# FFD.net
KiCad netlist of a schematic drawn in Altium Designer
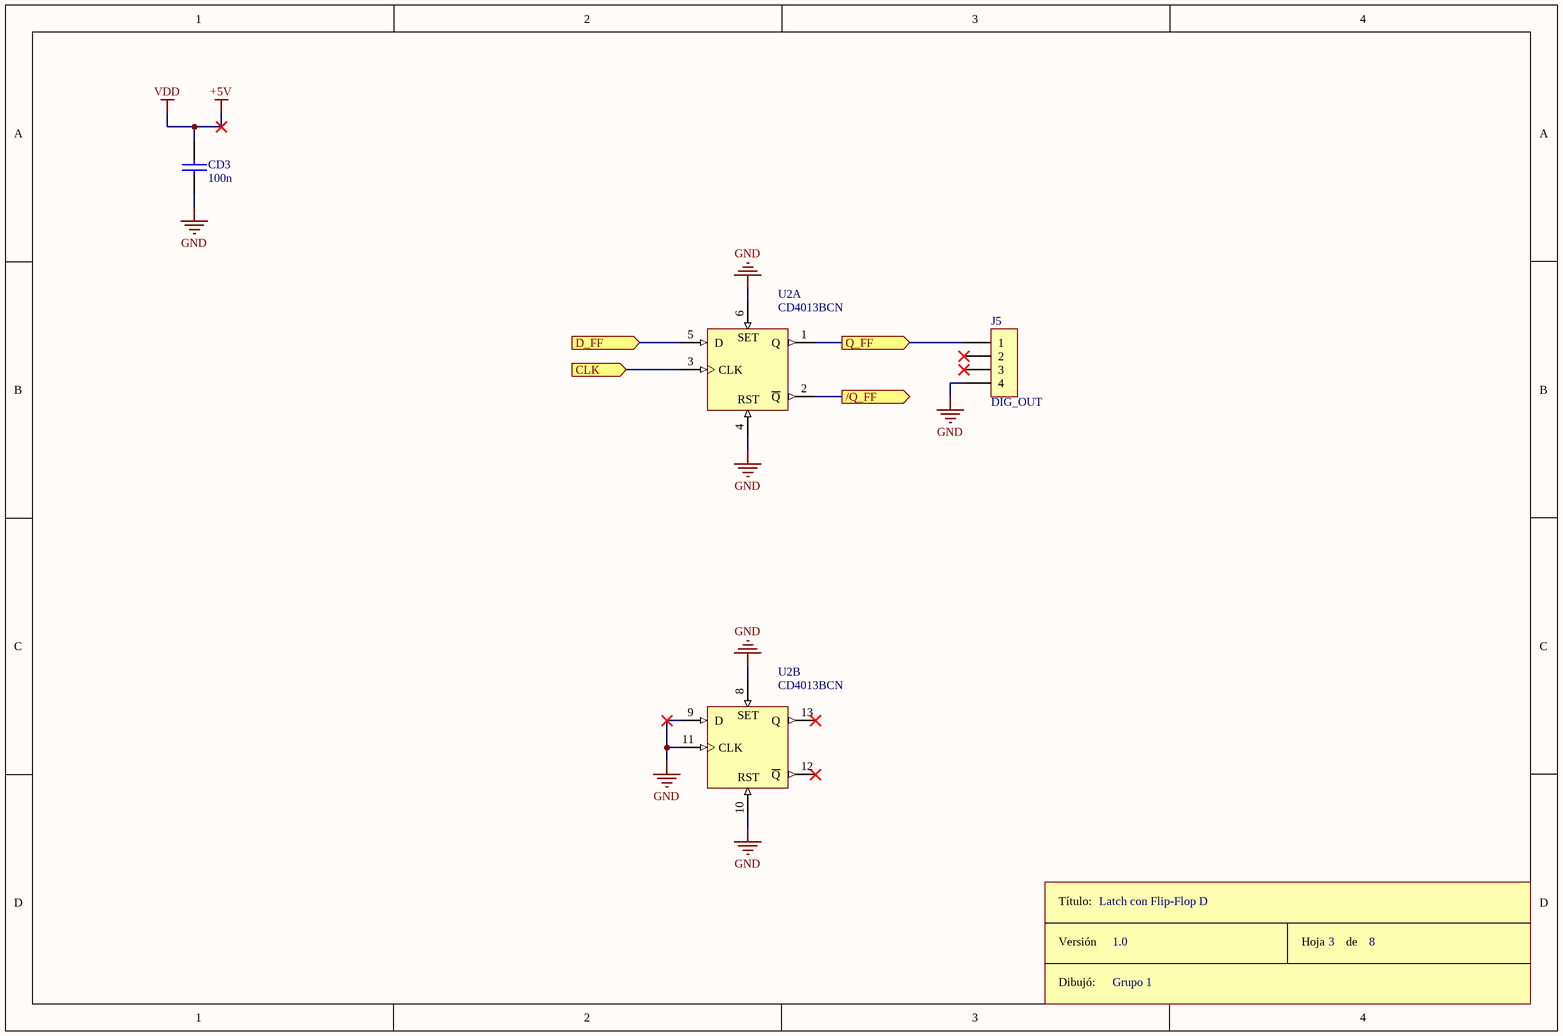
[diagram p0: FFD.SchDoc]

(export (version "E")
  (design (tool "Eeschema 10.0.6"))
  (components
    (comp (ref "CD3") (value "100n") (footprint "CAP100") (libsource (lib "LIBEBAL") (part "CAP")))
    (comp (ref "J5") (value "DIG_OUT") (footprint "SIP4") (libsource (lib "LIBEBAL") (part "CON4")))
    (comp (ref "ROT2") (value "Rótulo") (libsource (lib "LIB PIO IX") (part "Rótulo")))
    (comp (ref "U2")
      (value "CD4013BCN")
      (footprint "N14A")
      (description "Dual D-Type Flip-Flop")
      (fields (field (name "PUBLISHER") "Altium Limited"))
      (libsource (lib "FSC Logic Flip-Flop") (part "CD4013BCN"))
    )
  )
  (nets
    (net (code "1") (name "+5V") (class "Default")
      (node (ref "CD3") (pin "1") (pinfunction "1_1") (pintype "passive"))
      (node (ref "U2") (pin "14") (pinfunction "VDD_14") (pintype "power_in"))
    )
    (net (code "2") (name "/CLK") (class "Default")
      (node (ref "U2") (pin "3") (pinfunction "CLK_3") (pintype "input"))
    )
    (net (code "3") (name "/D_FF") (class "Default")
      (node (ref "U2") (pin "5") (pinfunction "D_5") (pintype "input"))
    )
    (net (code "4") (name "/Q_FF") (class "Default")
      (node (ref "J5") (pin "1") (pinfunction "1_1") (pintype "passive"))
      (node (ref "U2") (pin "1") (pinfunction "Q_1") (pintype "output"))
    )
    (net (code "5") (name "/{slash}Q_FF") (class "Default")
      (node (ref "U2") (pin "2") (pinfunction "~{Q}_2") (pintype "output"))
    )
    (net (code "6") (name "GND") (class "Default")
      (node (ref "CD3") (pin "2") (pinfunction "2_2") (pintype "passive"))
      (node (ref "J5") (pin "4") (pinfunction "4_4") (pintype "passive"))
      (node (ref "U2") (pin "10") (pinfunction "RST_10") (pintype "input"))
      (node (ref "U2") (pin "11") (pinfunction "CLK_11") (pintype "input"))
      (node (ref "U2") (pin "4") (pinfunction "RST_4") (pintype "input"))
      (node (ref "U2") (pin "6") (pinfunction "S_6") (pintype "input"))
      (node (ref "U2") (pin "7") (pinfunction "GND_7") (pintype "power_in"))
      (node (ref "U2") (pin "8") (pinfunction "S_8") (pintype "input"))
      (node (ref "U2") (pin "9") (pinfunction "D_9") (pintype "input"))
    )
    (net (code "7") (name "unconnected-(J5-Pad2)") (class "Default")
      (node (ref "J5") (pin "2") (pinfunction "2_2") (pintype "passive+no_connect"))
    )
    (net (code "8") (name "unconnected-(J5-Pad3)") (class "Default")
      (node (ref "J5") (pin "3") (pinfunction "3_3") (pintype "passive+no_connect"))
    )
    (net (code "9") (name "unconnected-(U2B-Q-Pad13)") (class "Default")
      (node (ref "U2") (pin "13") (pinfunction "Q_13") (pintype "output+no_connect"))
    )
    (net (code "10") (name "unconnected-(U2B-~{Q}-Pad12)") (class "Default")
      (node (ref "U2") (pin "12") (pinfunction "~{Q}_12") (pintype "output+no_connect"))
    )
  )
)
